# PCB-JOY-RCP.net
KiCad netlist of a schematic drawn in EAGLE
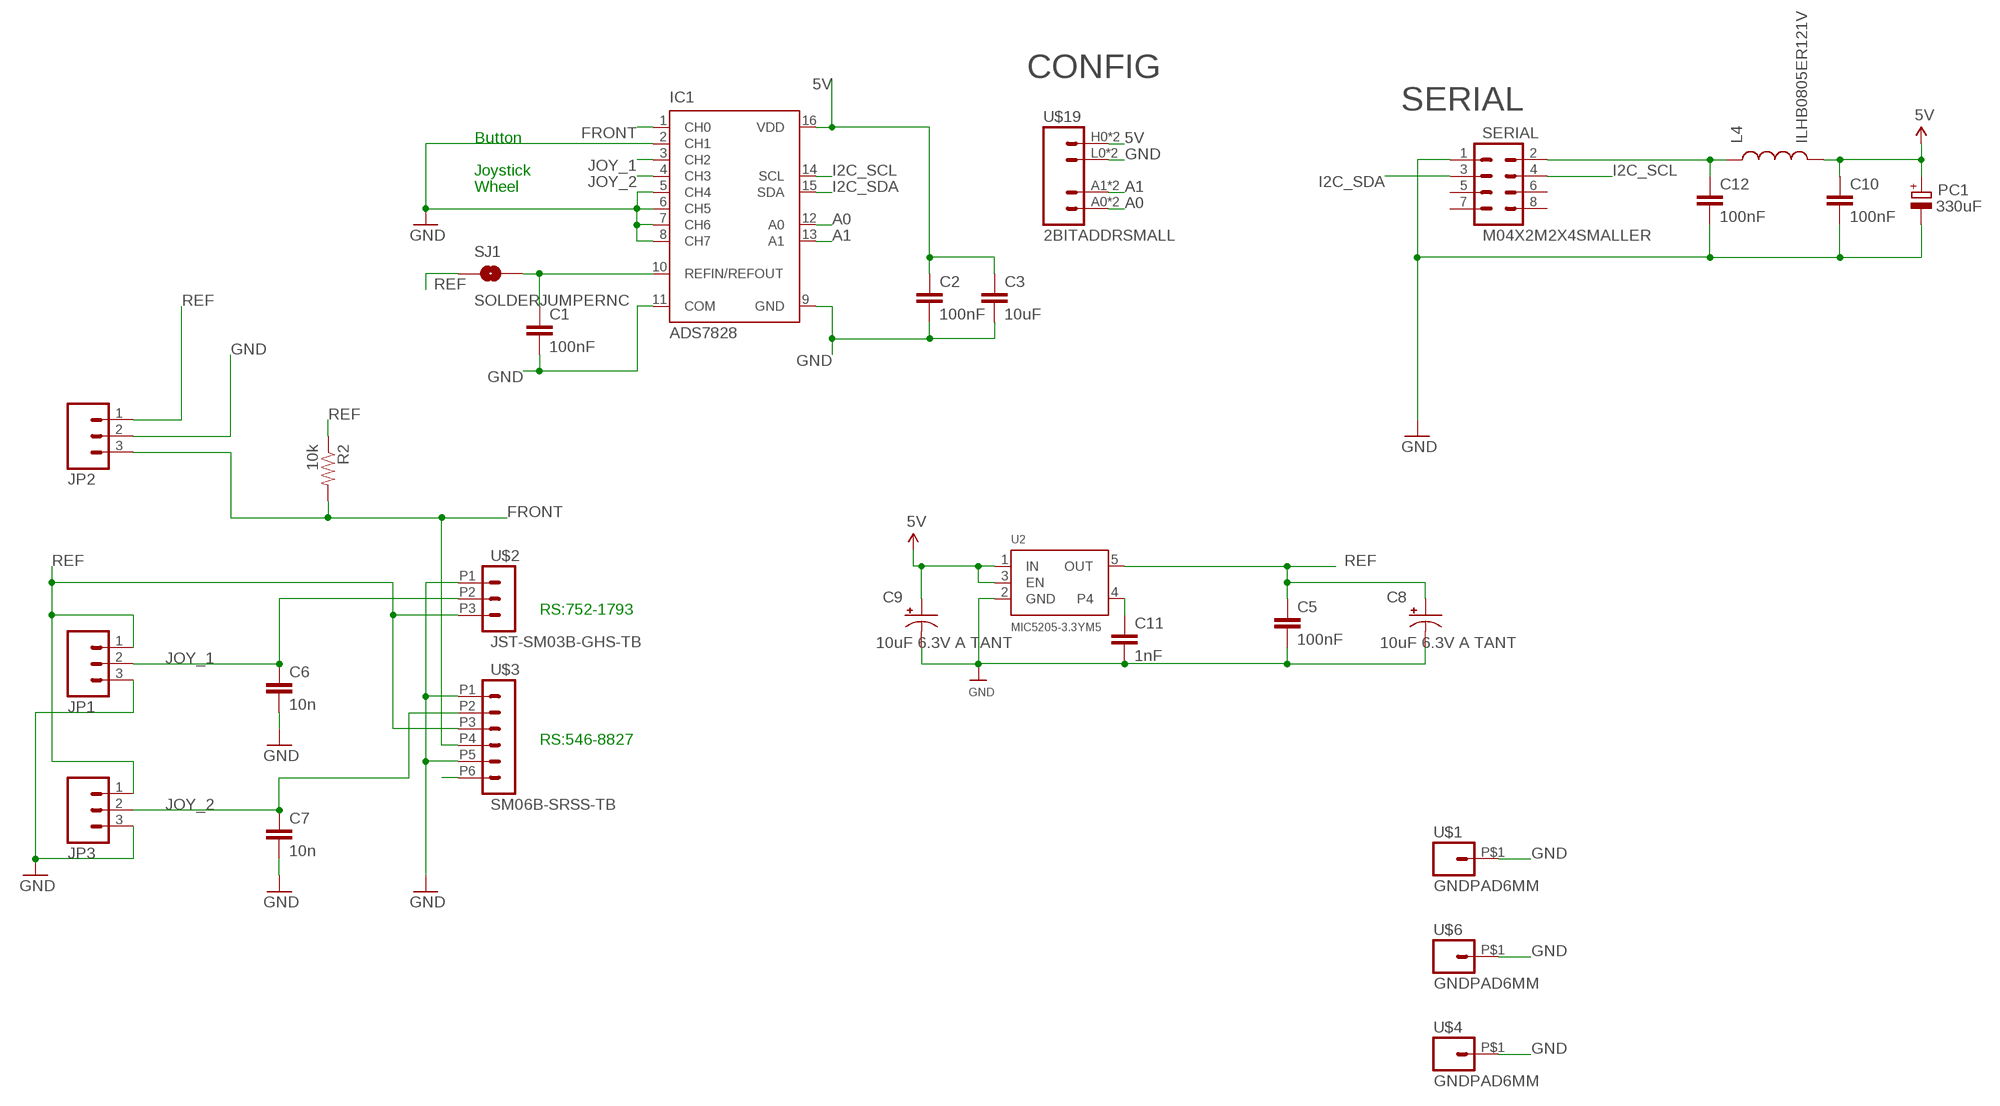
[diagram p0: schematic, sheet 1]

(export (version "E")
  (design (tool "Eeschema 10.0.6"))
  (components
    (comp (ref "C1")
      (value "100nF")
      (footprint "eagle-import:0603-CAP")
      (libsource (lib "eagle-import") (part "CAP0603-CAP"))
    )
    (comp (ref "C2")
      (value "100nF")
      (footprint "eagle-import:0603-CAP")
      (libsource (lib "eagle-import") (part "CAP0603-CAP"))
    )
    (comp (ref "C3")
      (value "10uF")
      (footprint "eagle-import:0805")
      (libsource (lib "eagle-import") (part "CAP0805"))
    )
    (comp (ref "C5")
      (value "100nF")
      (footprint "eagle-import:0603-CAP")
      (libsource (lib "eagle-import") (part "CAP0603-CAP"))
    )
    (comp (ref "C6")
      (value "10n")
      (footprint "eagle-import:0603-CAP")
      (libsource (lib "eagle-import") (part "CAP0603-CAP"))
    )
    (comp (ref "C7")
      (value "10n")
      (footprint "eagle-import:0603-CAP")
      (libsource (lib "eagle-import") (part "CAP0603-CAP"))
    )
    (comp (ref "C8")
      (value "10uF 6.3V A TANT")
      (footprint "eagle-import:EIA3216")
      (libsource (lib "eagle-import") (part "CAP_POL1206"))
    )
    (comp (ref "C9")
      (value "10uF 6.3V A TANT")
      (footprint "eagle-import:EIA3216")
      (libsource (lib "eagle-import") (part "CAP_POL1206"))
    )
    (comp (ref "C10")
      (value "100nF")
      (footprint "eagle-import:0603-CAP")
      (libsource (lib "eagle-import") (part "CAP0603-CAP"))
    )
    (comp (ref "C11")
      (value "1nF")
      (footprint "eagle-import:0603-CAP")
      (libsource (lib "eagle-import") (part "CAP0603-CAP"))
    )
    (comp (ref "C12")
      (value "100nF")
      (footprint "eagle-import:0603-CAP")
      (libsource (lib "eagle-import") (part "CAP0603-CAP"))
    )
    (comp (ref "IC1")
      (value "ADS7828")
      (footprint "eagle-import:TSSOP16-PW")
      (fields (field (name "MF") "TEXAS INSTRUMENTS") (field (name "MPN") "ADS7828E/250"))
      (libsource (lib "eagle-import") (part "ADS7828"))
    )
    (comp (ref "JP1")
      (value "M03PTH")
      (footprint "eagle-import:1X03")
      (libsource (lib "eagle-import") (part "M03PTH"))
    )
    (comp (ref "JP2")
      (value "M03PTH")
      (footprint "eagle-import:1X03")
      (libsource (lib "eagle-import") (part "M03PTH"))
    )
    (comp (ref "JP3")
      (value "M03PTH")
      (footprint "eagle-import:1X03")
      (libsource (lib "eagle-import") (part "M03PTH"))
    )
    (comp (ref "L4")
      (value "ILHB0805ER121V")
      (footprint "eagle-import:0805")
      (libsource (lib "eagle-import") (part "INDUCTOR0805"))
    )
    (comp (ref "PC1")
      (value "330uF")
      (footprint "eagle-import:PANASONIC_D")
      (libsource (lib "eagle-import") (part "CPOL-EUD"))
    )
    (comp (ref "R2")
      (value "10k")
      (footprint "eagle-import:0603-RES")
      (libsource (lib "eagle-import") (part "RESISTOR0603-RES"))
    )
    (comp (ref "SERIAL")
      (value "M04X2M2X4SMALLER")
      (footprint "eagle-import:M2X4SMALLER")
      (libsource (lib "eagle-import") (part "M04X2M2X4SMALLER"))
    )
    (comp (ref "SJ1")
      (value "SOLDERJUMPERNC")
      (footprint "eagle-import:SJ_2S")
      (libsource (lib "eagle-import") (part "SOLDERJUMPERNC"))
    )
    (comp (ref "U$1")
      (value "GNDPAD6MM")
      (footprint "eagle-import:3.2MMPAD6MM")
      (libsource (lib "eagle-import") (part "GNDPAD6MM"))
    )
    (comp (ref "U$2")
      (value "JST-SM03B-GHS-TB")
      (footprint "eagle-import:JST-SM03B-GHS-TB")
      (libsource (lib "eagle-import") (part "JST-SM03B-GHS-TB"))
    )
    (comp (ref "U$3")
      (value "SM06B-SRSS-TB")
      (footprint "eagle-import:JST-SM06B-SRSS-TB")
      (libsource (lib "eagle-import") (part "SM06B-SRSS-TB"))
    )
    (comp (ref "U$4")
      (value "GNDPAD6MM")
      (footprint "eagle-import:3.2MMPAD6MM")
      (libsource (lib "eagle-import") (part "GNDPAD6MM"))
    )
    (comp (ref "U$6")
      (value "GNDPAD6MM")
      (footprint "eagle-import:3.2MMPAD6MM")
      (libsource (lib "eagle-import") (part "GNDPAD6MM"))
    )
    (comp (ref "U$19")
      (value "2BITADDRSMALL")
      (footprint "eagle-import:2BITADDR_SMALL")
      (libsource (lib "eagle-import") (part "2BITADDRSMALL"))
    )
    (comp (ref "U2")
      (value "MIC5205-3.3YM5")
      (footprint "eagle-import:SOT23-5")
      (libsource (lib "eagle-import") (part "VREG_SOT23-5"))
    )
  )
  (nets
    (net (code "1") (name "/A0") (class "Default")
      (node (ref "IC1") (pin "12") (pinfunction "A0_12") (pintype "input"))
      (node (ref "U$19") (pin "A0") (pinfunction "A1_A0") (pintype "passive"))
      (node (ref "U$19") (pin "AS0") (pinfunction "A1_AS0") (pintype "passive"))
    )
    (net (code "2") (name "/A1") (class "Default")
      (node (ref "IC1") (pin "13") (pinfunction "A1_13") (pintype "input"))
      (node (ref "U$19") (pin "A1") (pinfunction "A2_A1") (pintype "passive"))
      (node (ref "U$19") (pin "AS1") (pinfunction "A2_AS1") (pintype "passive"))
    )
    (net (code "3") (name "/FRONT") (class "Default")
      (node (ref "IC1") (pin "1") (pinfunction "CH0_1") (pintype "input"))
      (node (ref "JP2") (pin "3") (pinfunction "3_3") (pintype "passive"))
      (node (ref "R2") (pin "2") (pinfunction "2_2") (pintype "passive"))
      (node (ref "U$3") (pin "P4") (pinfunction "4_P4") (pintype "passive"))
    )
    (net (code "4") (name "/I2C_SCL") (class "Default")
      (node (ref "IC1") (pin "14") (pinfunction "SCL_14") (pintype "input"))
      (node (ref "SERIAL") (pin "4") (pinfunction "4_4") (pintype "passive"))
    )
    (net (code "5") (name "/I2C_SDA") (class "Default")
      (node (ref "IC1") (pin "15") (pinfunction "SDA_15") (pintype "bidirectional"))
      (node (ref "SERIAL") (pin "3") (pinfunction "3_3") (pintype "passive"))
    )
    (net (code "6") (name "/JOY_1") (class "Default")
      (node (ref "C6") (pin "1") (pinfunction "1_1") (pintype "passive"))
      (node (ref "IC1") (pin "3") (pinfunction "CH2_3") (pintype "input"))
      (node (ref "JP1") (pin "2") (pinfunction "2_2") (pintype "passive"))
      (node (ref "U$2") (pin "P2") (pinfunction "2_P2") (pintype "passive"))
    )
    (net (code "7") (name "/JOY_2") (class "Default")
      (node (ref "C7") (pin "1") (pinfunction "1_1") (pintype "passive"))
      (node (ref "IC1") (pin "4") (pinfunction "CH3_4") (pintype "input"))
      (node (ref "JP3") (pin "2") (pinfunction "2_2") (pintype "passive"))
      (node (ref "U$3") (pin "P2") (pinfunction "2_P2") (pintype "passive"))
    )
    (net (code "8") (name "/REF") (class "Default")
      (node (ref "C5") (pin "1") (pinfunction "1_1") (pintype "passive"))
      (node (ref "C8") (pin "A") (pinfunction "+_A") (pintype "passive"))
      (node (ref "JP1") (pin "1") (pinfunction "1_1") (pintype "passive"))
      (node (ref "JP2") (pin "1") (pinfunction "1_1") (pintype "passive"))
      (node (ref "JP3") (pin "1") (pinfunction "1_1") (pintype "passive"))
      (node (ref "R2") (pin "1") (pinfunction "1_1") (pintype "passive"))
      (node (ref "SJ1") (pin "1") (pinfunction "1_1") (pintype "passive"))
      (node (ref "U$2") (pin "P3") (pinfunction "3_P3") (pintype "passive"))
      (node (ref "U$3") (pin "P3") (pinfunction "3_P3") (pintype "passive"))
      (node (ref "U2") (pin "5") (pinfunction "OUT_5") (pintype "bidirectional"))
    )
    (net (code "9") (name "5V") (class "Default")
      (node (ref "C10") (pin "1") (pinfunction "1_1") (pintype "passive"))
      (node (ref "C2") (pin "1") (pinfunction "1_1") (pintype "passive"))
      (node (ref "C3") (pin "1") (pinfunction "1_1") (pintype "passive"))
      (node (ref "C9") (pin "A") (pinfunction "+_A") (pintype "passive"))
      (node (ref "IC1") (pin "16") (pinfunction "VDD_16") (pintype "power_in"))
      (node (ref "L4") (pin "2") (pinfunction "2_2") (pintype "passive"))
      (node (ref "PC1") (pin "+") (pinfunction "+_+") (pintype "passive"))
      (node (ref "U$19") (pin "H0") (pinfunction "VCC_H0") (pintype "passive"))
      (node (ref "U$19") (pin "H1") (pinfunction "VCC_H1") (pintype "passive"))
      (node (ref "U2") (pin "1") (pinfunction "IN_1") (pintype "bidirectional"))
      (node (ref "U2") (pin "3") (pinfunction "EN_3") (pintype "bidirectional"))
    )
    (net (code "10") (name "GND") (class "Default")
      (node (ref "C1") (pin "2") (pinfunction "2_2") (pintype "passive"))
      (node (ref "C10") (pin "2") (pinfunction "2_2") (pintype "passive"))
      (node (ref "C11") (pin "2") (pinfunction "2_2") (pintype "passive"))
      (node (ref "C12") (pin "2") (pinfunction "2_2") (pintype "passive"))
      (node (ref "C2") (pin "2") (pinfunction "2_2") (pintype "passive"))
      (node (ref "C3") (pin "2") (pinfunction "2_2") (pintype "passive"))
      (node (ref "C5") (pin "2") (pinfunction "2_2") (pintype "passive"))
      (node (ref "C6") (pin "2") (pinfunction "2_2") (pintype "passive"))
      (node (ref "C7") (pin "2") (pinfunction "2_2") (pintype "passive"))
      (node (ref "C8") (pin "C") (pinfunction "-_C") (pintype "passive"))
      (node (ref "C9") (pin "C") (pinfunction "-_C") (pintype "passive"))
      (node (ref "IC1") (pin "11") (pinfunction "COM_11") (pintype "input"))
      (node (ref "IC1") (pin "2") (pinfunction "CH1_2") (pintype "input"))
      (node (ref "IC1") (pin "5") (pinfunction "CH4_5") (pintype "input"))
      (node (ref "IC1") (pin "6") (pinfunction "CH5_6") (pintype "input"))
      (node (ref "IC1") (pin "7") (pinfunction "CH6_7") (pintype "input"))
      (node (ref "IC1") (pin "8") (pinfunction "CH7_8") (pintype "input"))
      (node (ref "IC1") (pin "9") (pinfunction "GND_9") (pintype "power_in"))
      (node (ref "JP1") (pin "3") (pinfunction "3_3") (pintype "passive"))
      (node (ref "JP2") (pin "2") (pinfunction "2_2") (pintype "passive"))
      (node (ref "JP3") (pin "3") (pinfunction "3_3") (pintype "passive"))
      (node (ref "PC1") (pin "-") (pinfunction "-_-") (pintype "passive"))
      (node (ref "SERIAL") (pin "1") (pinfunction "1_1") (pintype "passive"))
      (node (ref "U$1") (pin "P$1") (pinfunction "1_P$1") (pintype "passive"))
      (node (ref "U$19") (pin "L0") (pinfunction "GND_L0") (pintype "passive"))
      (node (ref "U$19") (pin "L1") (pinfunction "GND_L1") (pintype "passive"))
      (node (ref "U$2") (pin "P1") (pinfunction "1_P1") (pintype "passive"))
      (node (ref "U$3") (pin "P1") (pinfunction "1_P1") (pintype "passive"))
      (node (ref "U$3") (pin "P5") (pinfunction "5_P5") (pintype "passive"))
      (node (ref "U$4") (pin "P$1") (pinfunction "1_P$1") (pintype "passive"))
      (node (ref "U$6") (pin "P$1") (pinfunction "1_P$1") (pintype "passive"))
      (node (ref "U2") (pin "2") (pinfunction "GND_2") (pintype "bidirectional"))
    )
    (net (code "11") (name "Net-(C12-Pad1)") (class "Default")
      (node (ref "C12") (pin "1") (pinfunction "1_1") (pintype "passive"))
      (node (ref "L4") (pin "1") (pinfunction "1_1") (pintype "passive"))
      (node (ref "SERIAL") (pin "2") (pinfunction "2_2") (pintype "passive"))
    )
    (net (code "12") (name "Net-(IC1-REFIN{slash}REFOUT)") (class "Default")
      (node (ref "C1") (pin "1") (pinfunction "1_1") (pintype "passive"))
      (node (ref "IC1") (pin "10") (pinfunction "REFIN/REFOUT_10") (pintype "passive"))
      (node (ref "SJ1") (pin "2") (pinfunction "2_2") (pintype "passive"))
    )
    (net (code "13") (name "Net-(U2-P4)") (class "Default")
      (node (ref "C11") (pin "1") (pinfunction "1_1") (pintype "passive"))
      (node (ref "U2") (pin "4") (pinfunction "P4_4") (pintype "bidirectional"))
    )
    (net (code "14") (name "unconnected-(SERIAL-Pad5)") (class "Default")
      (node (ref "SERIAL") (pin "5") (pinfunction "5_5") (pintype "passive"))
    )
    (net (code "15") (name "unconnected-(SERIAL-Pad6)") (class "Default")
      (node (ref "SERIAL") (pin "6") (pinfunction "6_6") (pintype "passive"))
    )
    (net (code "16") (name "unconnected-(SERIAL-Pad7)") (class "Default")
      (node (ref "SERIAL") (pin "7") (pinfunction "7_7") (pintype "passive"))
    )
    (net (code "17") (name "unconnected-(SERIAL-Pad8)") (class "Default")
      (node (ref "SERIAL") (pin "8") (pinfunction "8_8") (pintype "passive"))
    )
    (net (code "18") (name "unconnected-(U$3-6-PadP6)") (class "Default")
      (node (ref "U$3") (pin "P6") (pinfunction "6_P6") (pintype "passive"))
    )
  )
)
